# hackeeg-connector-32.net
KiCad netlist of a schematic drawn in EAGLE
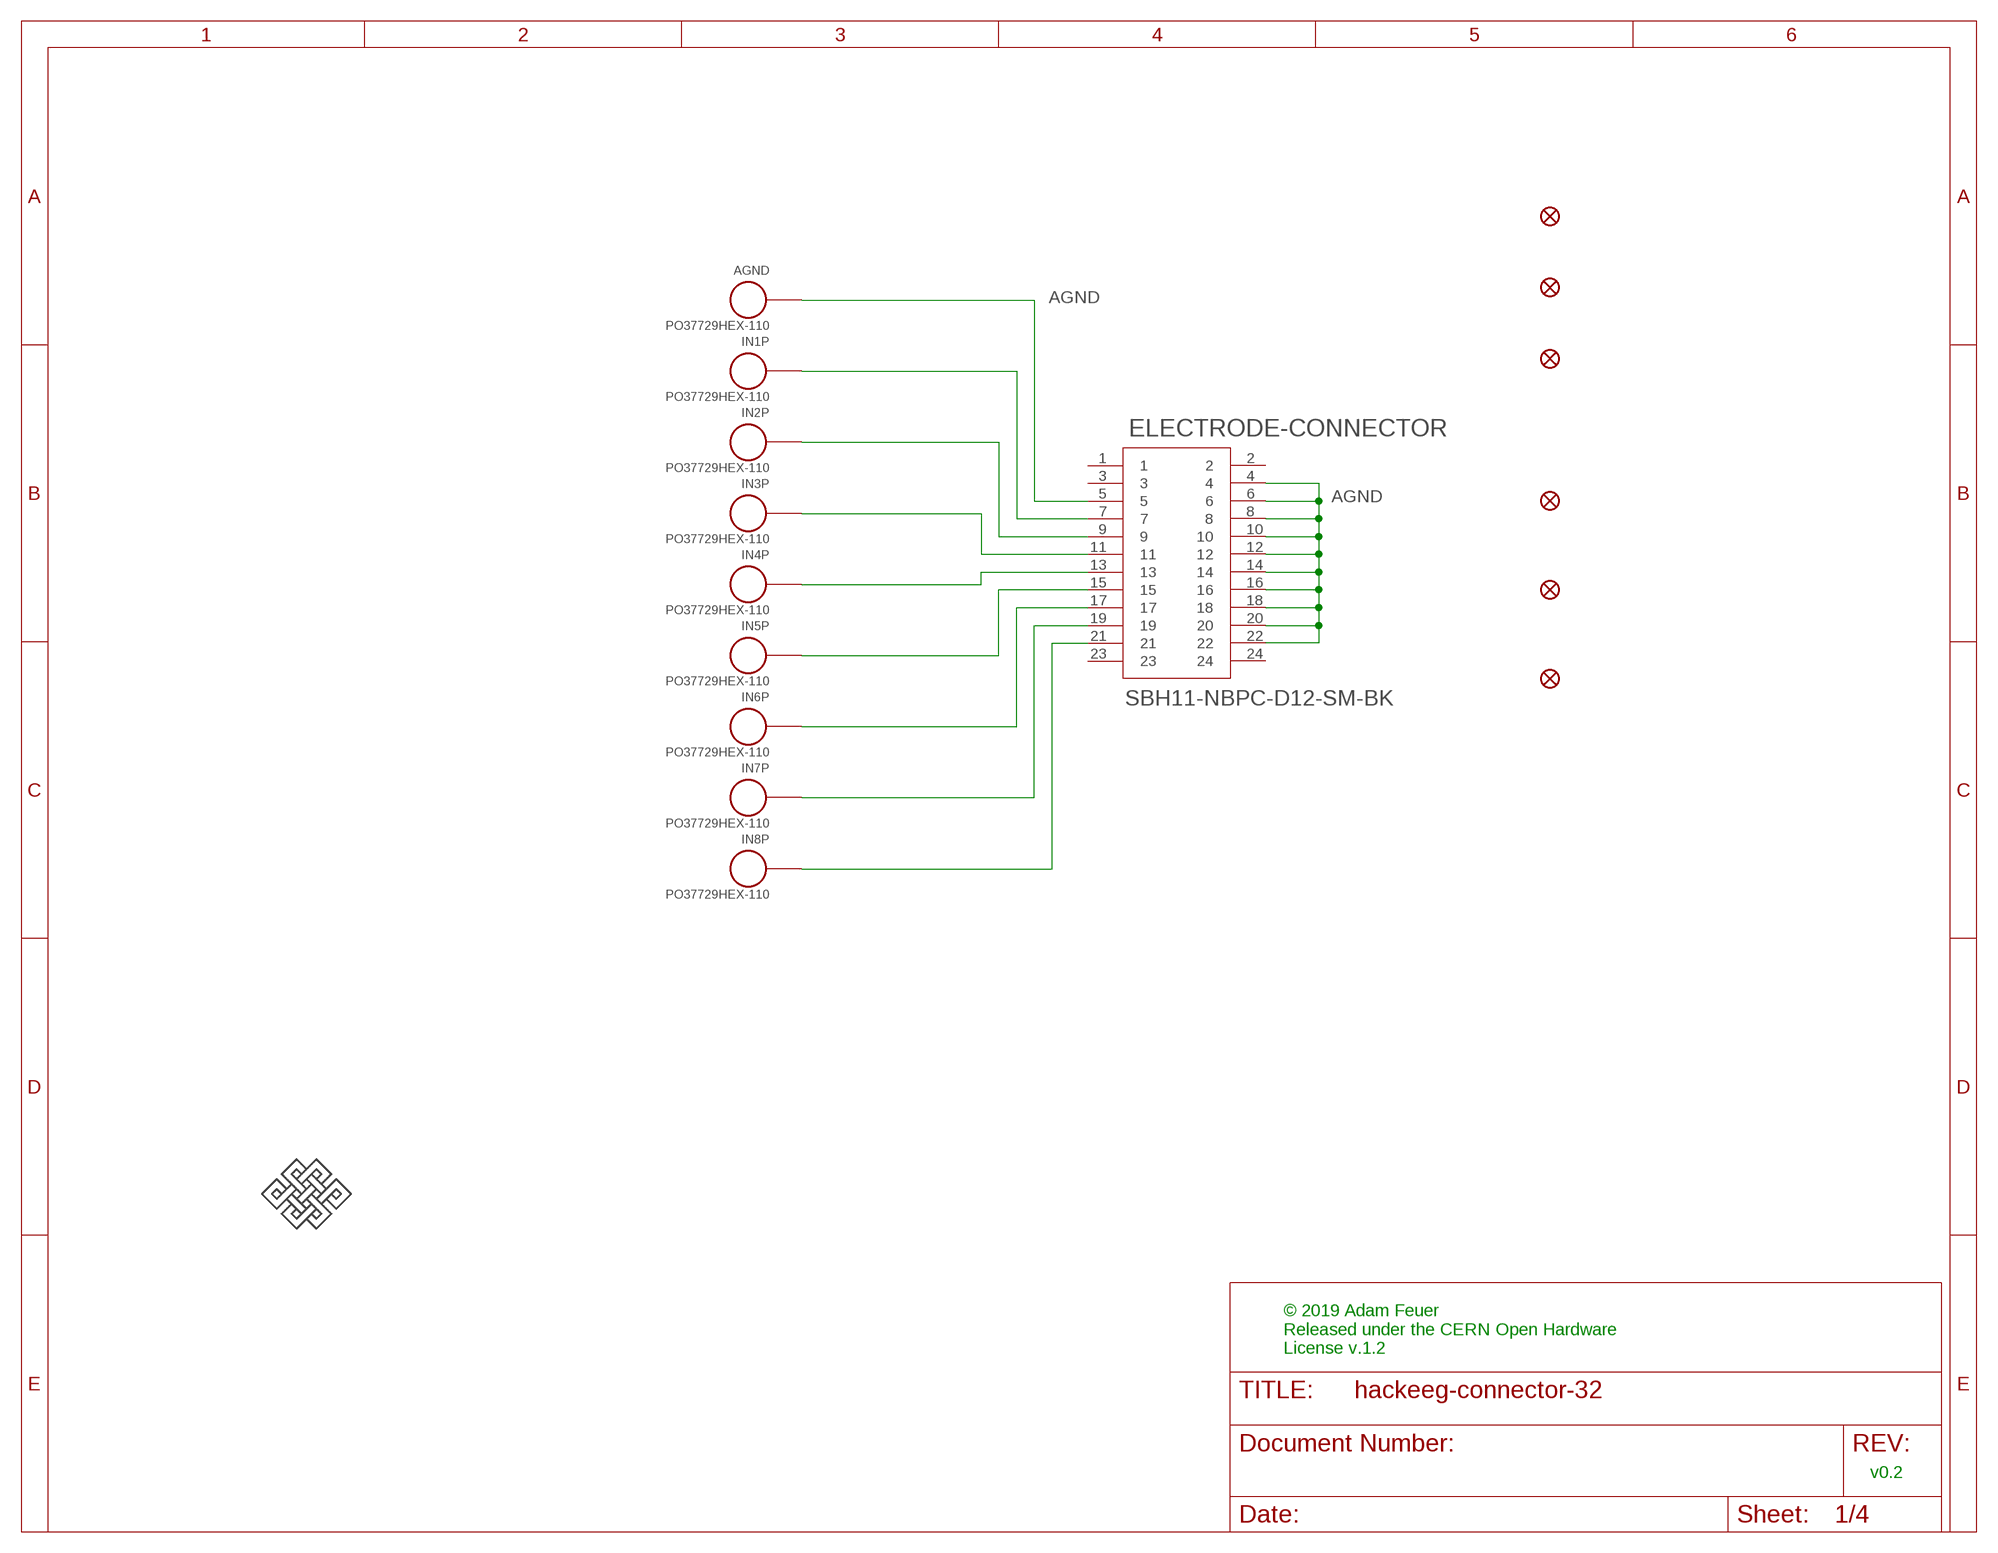
[diagram p0: schematic, sheet 1]
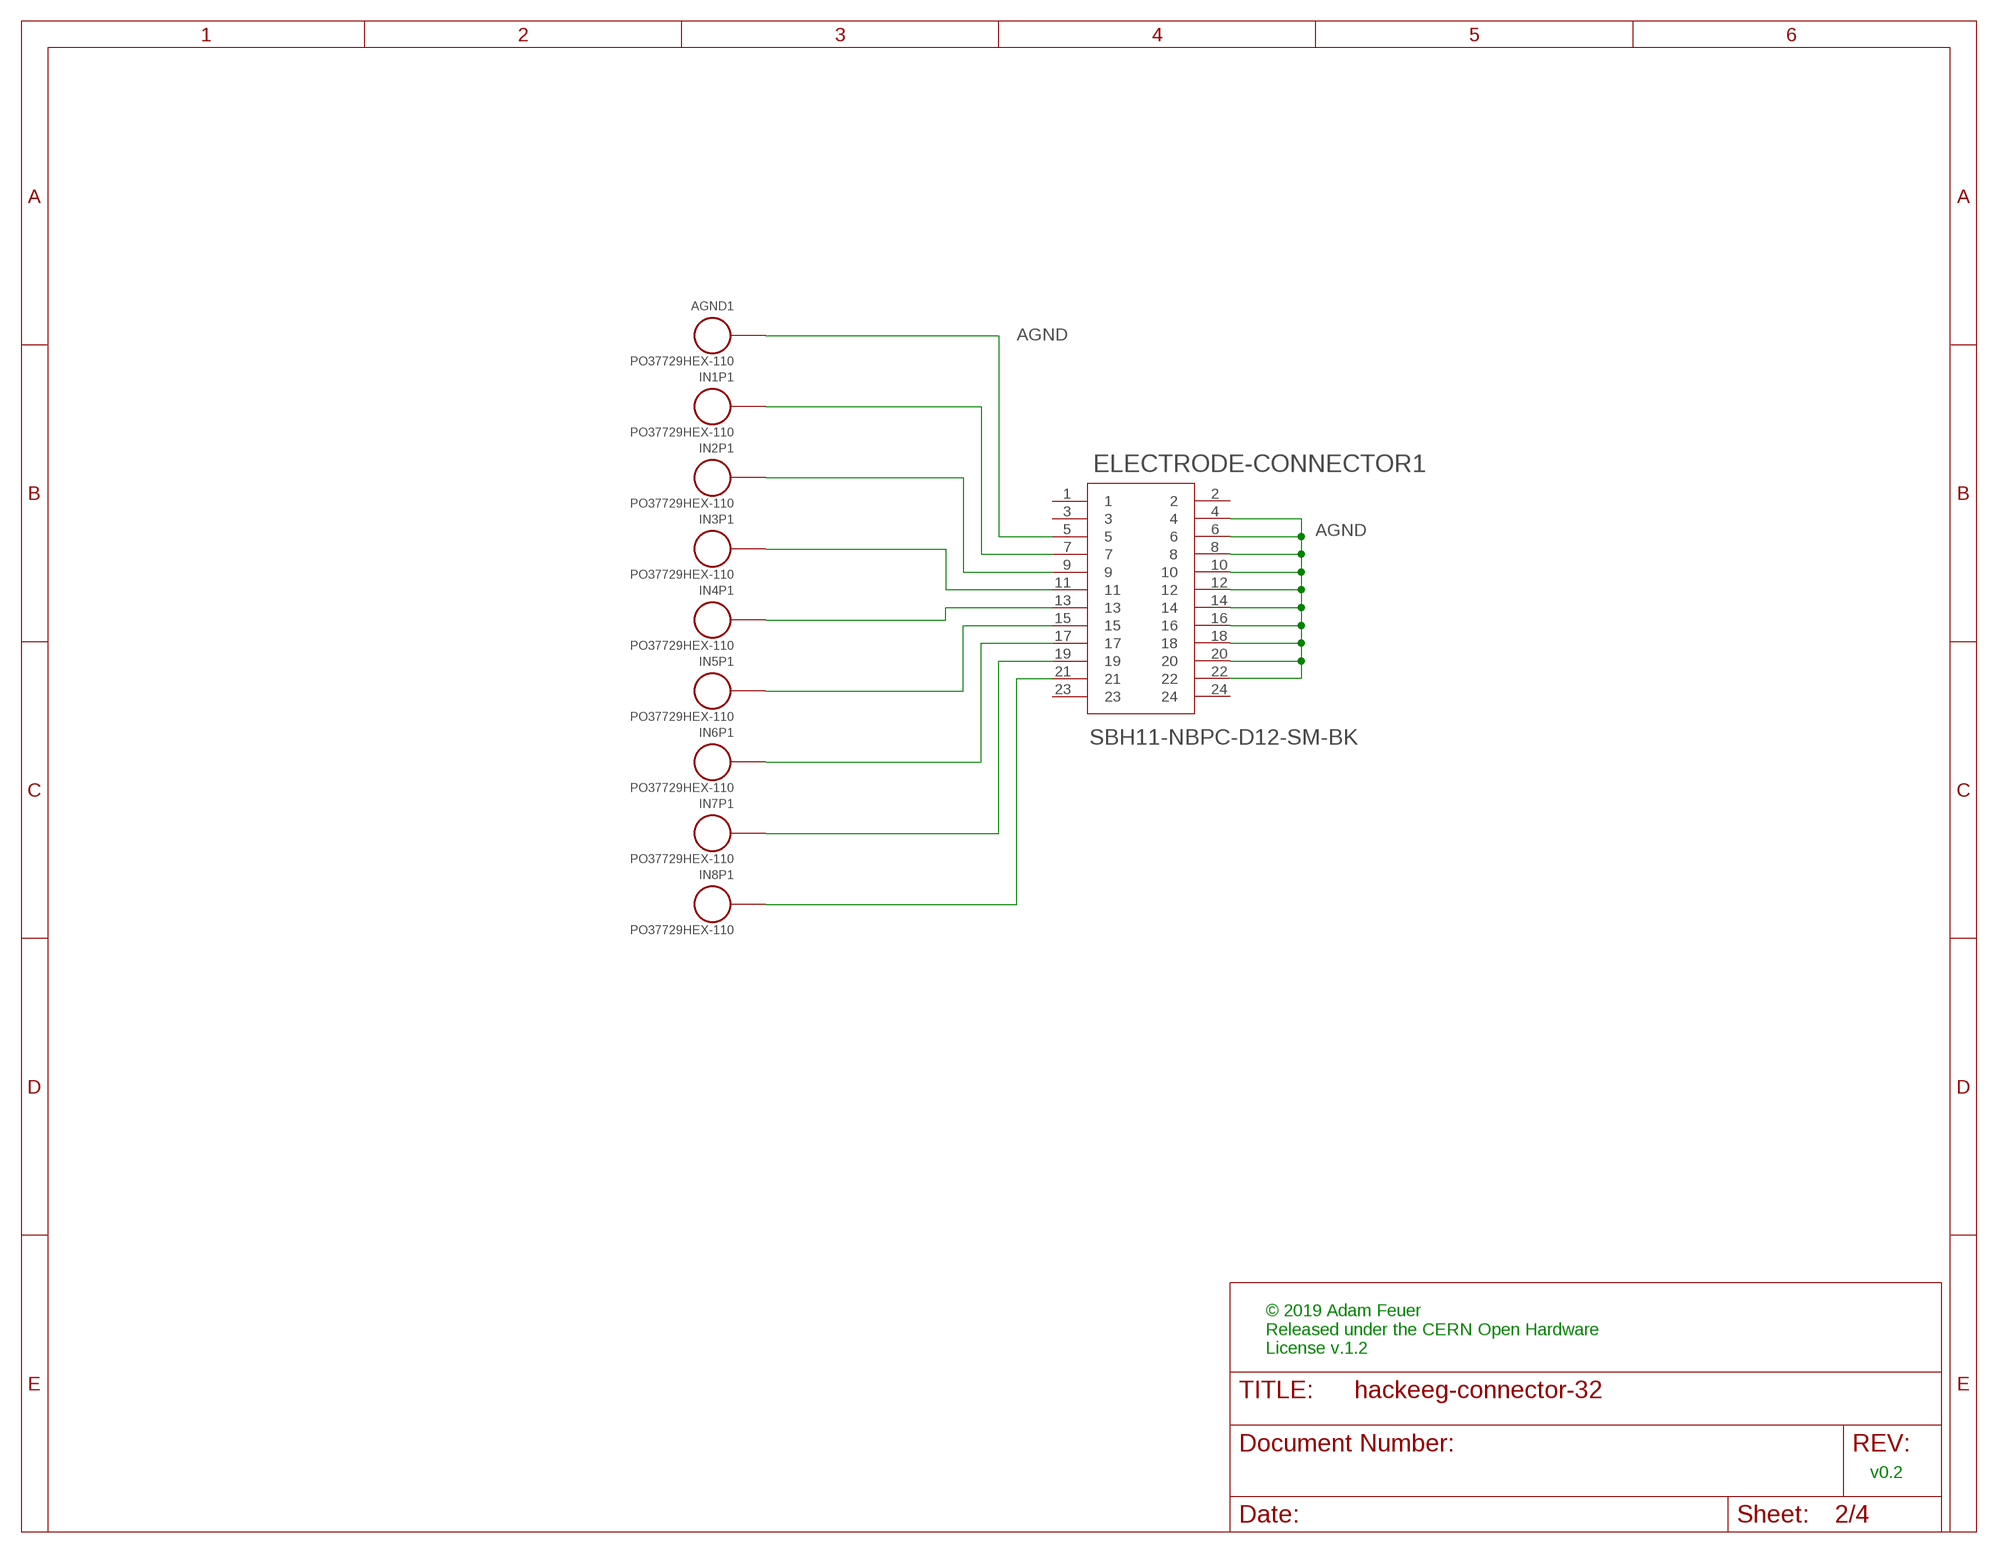
[diagram p1: schematic, sheet 2]
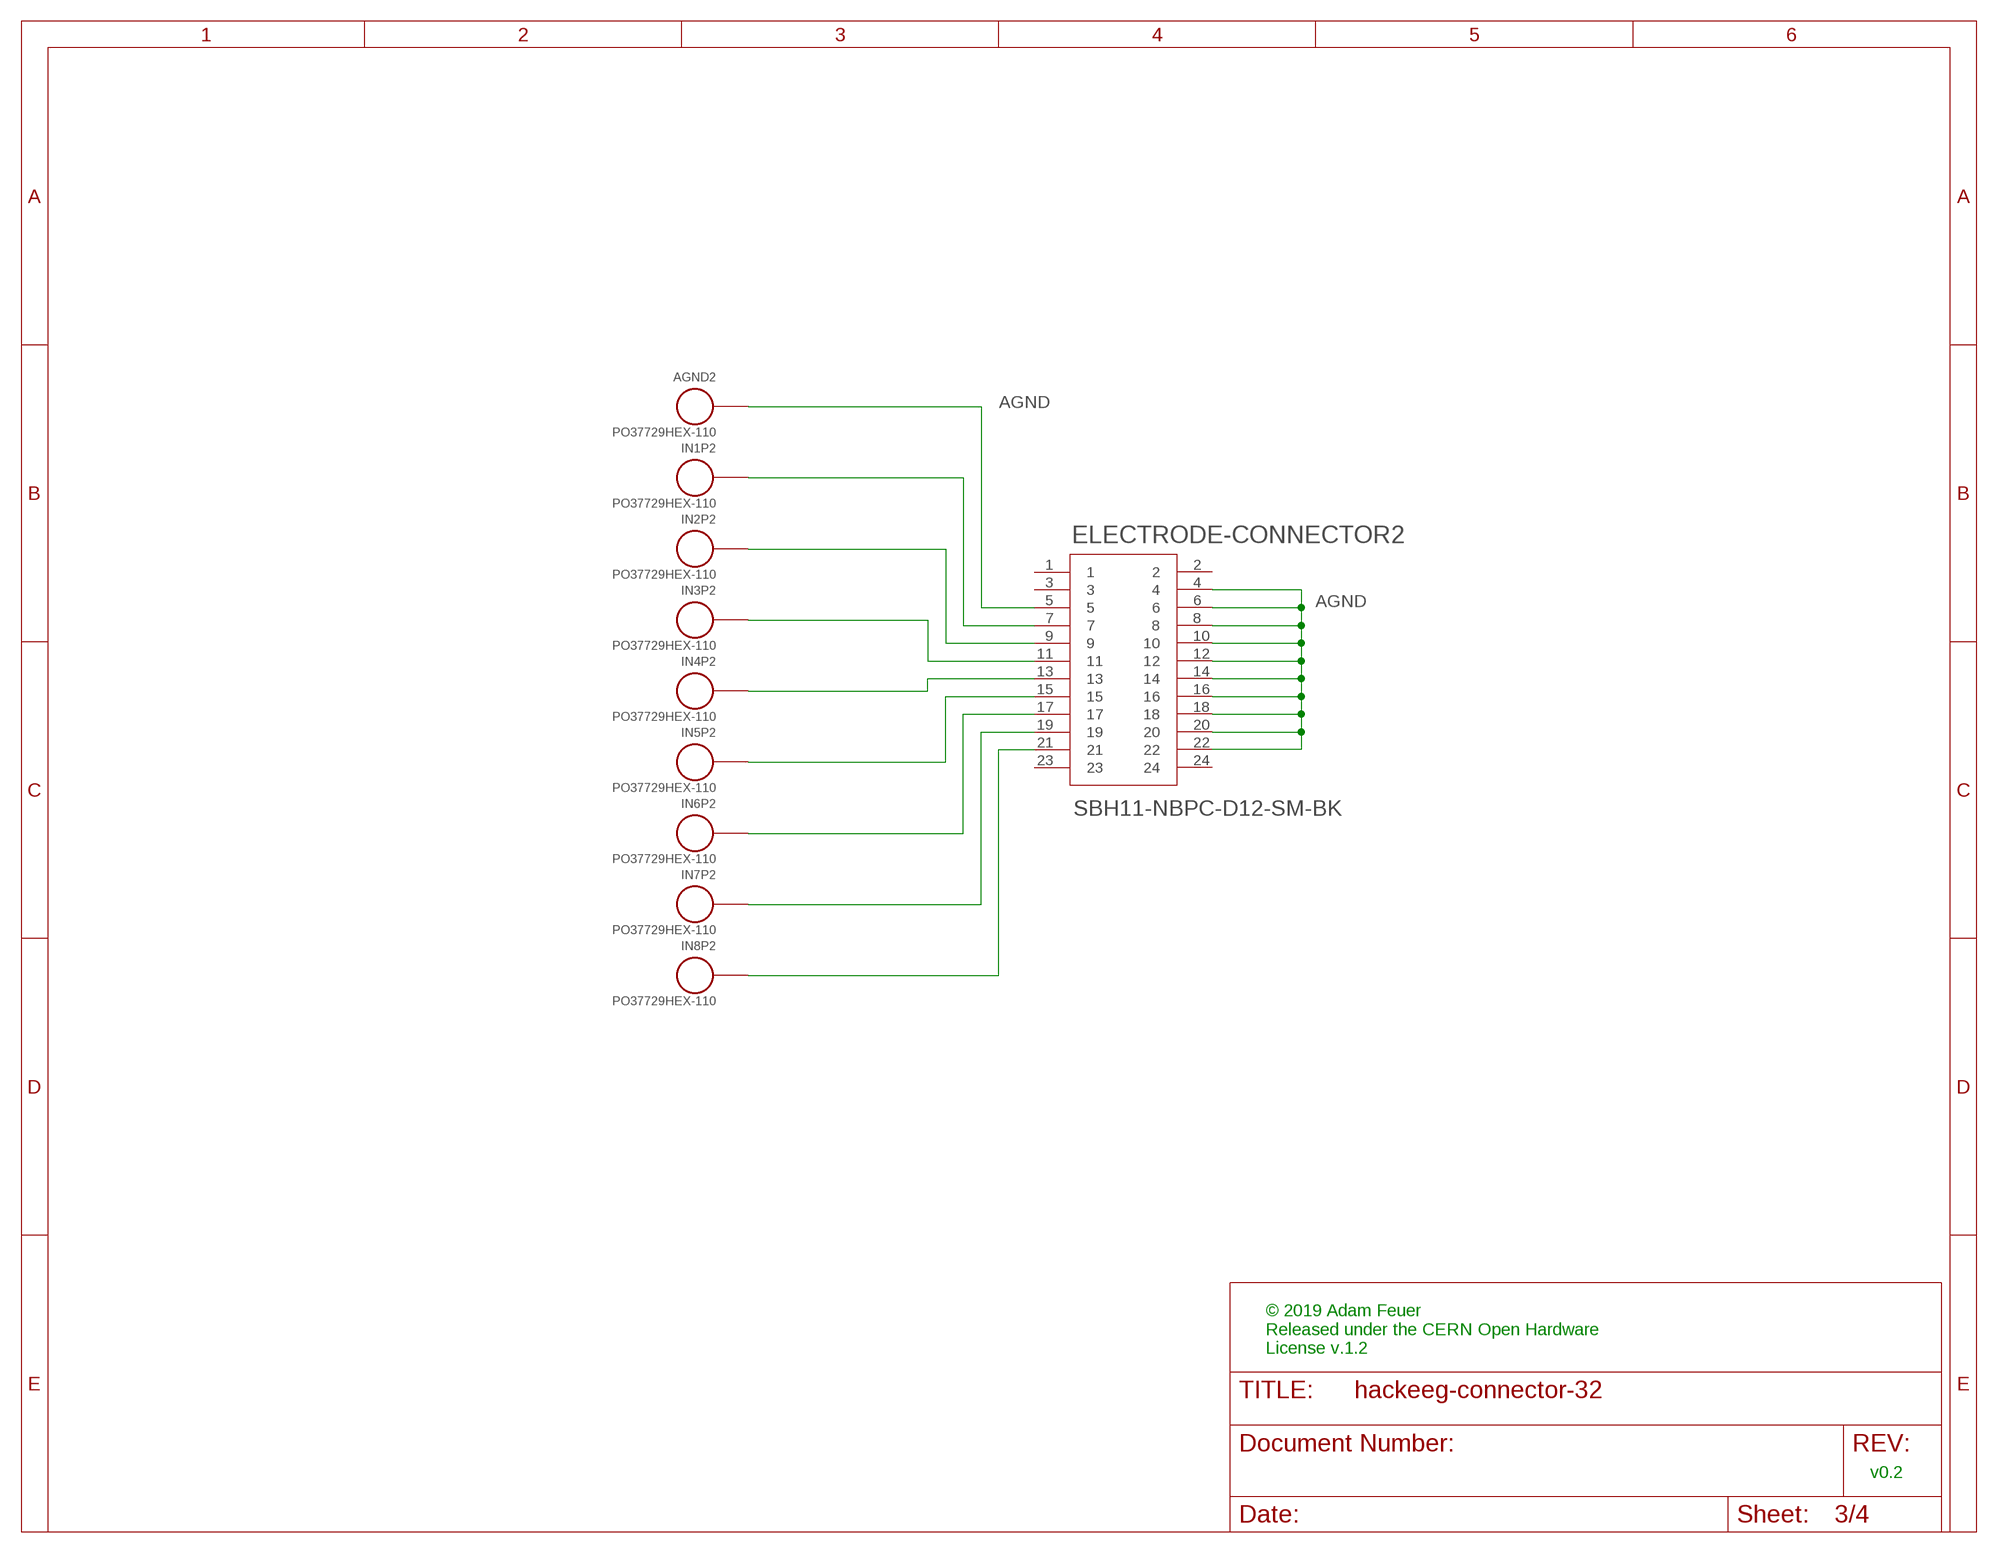
[diagram p2: schematic, sheet 3]
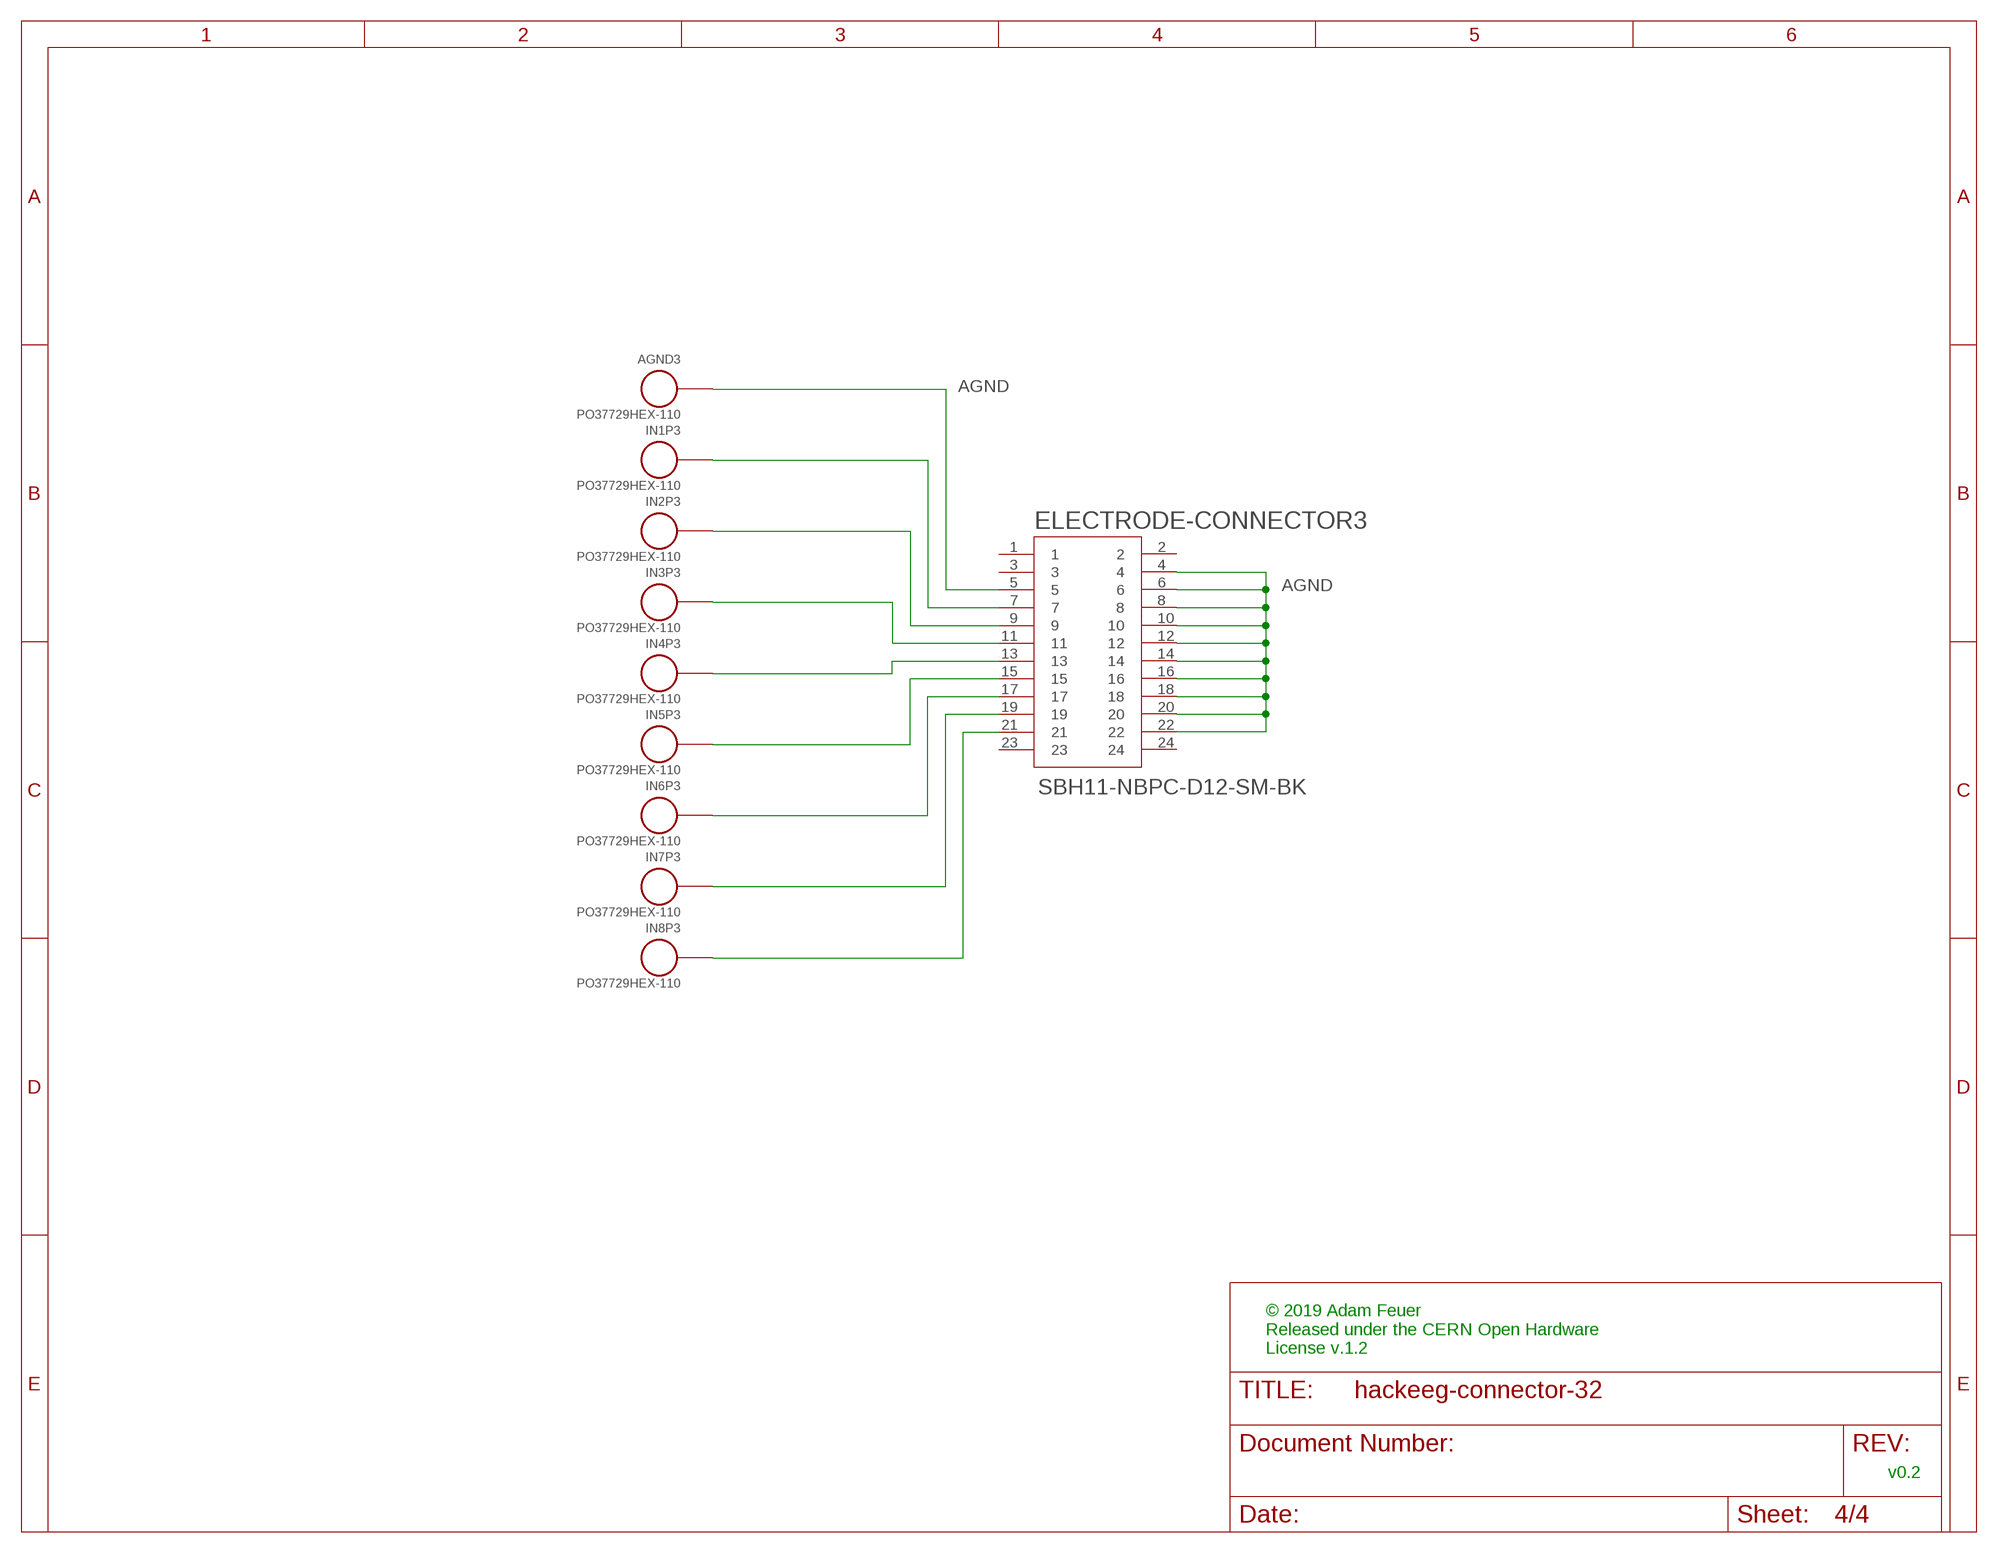
[diagram p3: schematic, sheet 4]

(export (version "E")
  (design (tool "Eeschema 10.0.6"))
  (components
    (comp (ref "AGND2")
      (value "PO37729HEX-110")
      (footprint "eagle-import:HEX-110")
      (libsource (lib "eagle-import") (part "PO37729HEX-110"))
    )
    (comp (ref "ELECTRODE-CONNECTOR2")
      (value "SBH11-NBPC-D12-SM-BK")
      (footprint "eagle-import:SULLINS_SBH11-NBPC-D12-SM-BK")
      (fields (field (name "MF") "Sullins Connector"))
      (libsource (lib "eagle-import") (part "SBH11-NBPC-D12-SM-BK"))
    )
    (comp (ref "IN1P2")
      (value "PO37729HEX-110")
      (footprint "eagle-import:HEX-110")
      (libsource (lib "eagle-import") (part "PO37729HEX-110"))
    )
    (comp (ref "IN2P2")
      (value "PO37729HEX-110")
      (footprint "eagle-import:HEX-110")
      (libsource (lib "eagle-import") (part "PO37729HEX-110"))
    )
    (comp (ref "IN3P2")
      (value "PO37729HEX-110")
      (footprint "eagle-import:HEX-110")
      (libsource (lib "eagle-import") (part "PO37729HEX-110"))
    )
    (comp (ref "IN4P2")
      (value "PO37729HEX-110")
      (footprint "eagle-import:HEX-110")
      (libsource (lib "eagle-import") (part "PO37729HEX-110"))
    )
    (comp (ref "IN5P2")
      (value "PO37729HEX-110")
      (footprint "eagle-import:HEX-110")
      (libsource (lib "eagle-import") (part "PO37729HEX-110"))
    )
    (comp (ref "IN6P2")
      (value "PO37729HEX-110")
      (footprint "eagle-import:HEX-110")
      (libsource (lib "eagle-import") (part "PO37729HEX-110"))
    )
    (comp (ref "IN7P2")
      (value "PO37729HEX-110")
      (footprint "eagle-import:HEX-110")
      (libsource (lib "eagle-import") (part "PO37729HEX-110"))
    )
    (comp (ref "IN8P2")
      (value "PO37729HEX-110")
      (footprint "eagle-import:HEX-110")
      (libsource (lib "eagle-import") (part "PO37729HEX-110"))
    )
    (comp (ref "AGND3")
      (value "PO37729HEX-110")
      (footprint "eagle-import:HEX-110")
      (libsource (lib "eagle-import") (part "PO37729HEX-110"))
    )
    (comp (ref "ELECTRODE-CONNECTOR3")
      (value "SBH11-NBPC-D12-SM-BK")
      (footprint "eagle-import:SULLINS_SBH11-NBPC-D12-SM-BK")
      (fields (field (name "MF") "Sullins Connector"))
      (libsource (lib "eagle-import") (part "SBH11-NBPC-D12-SM-BK"))
    )
    (comp (ref "IN1P3")
      (value "PO37729HEX-110")
      (footprint "eagle-import:HEX-110")
      (libsource (lib "eagle-import") (part "PO37729HEX-110"))
    )
    (comp (ref "IN2P3")
      (value "PO37729HEX-110")
      (footprint "eagle-import:HEX-110")
      (libsource (lib "eagle-import") (part "PO37729HEX-110"))
    )
    (comp (ref "IN3P3")
      (value "PO37729HEX-110")
      (footprint "eagle-import:HEX-110")
      (libsource (lib "eagle-import") (part "PO37729HEX-110"))
    )
    (comp (ref "IN4P3")
      (value "PO37729HEX-110")
      (footprint "eagle-import:HEX-110")
      (libsource (lib "eagle-import") (part "PO37729HEX-110"))
    )
    (comp (ref "IN5P3")
      (value "PO37729HEX-110")
      (footprint "eagle-import:HEX-110")
      (libsource (lib "eagle-import") (part "PO37729HEX-110"))
    )
    (comp (ref "IN6P3")
      (value "PO37729HEX-110")
      (footprint "eagle-import:HEX-110")
      (libsource (lib "eagle-import") (part "PO37729HEX-110"))
    )
    (comp (ref "IN7P3")
      (value "PO37729HEX-110")
      (footprint "eagle-import:HEX-110")
      (libsource (lib "eagle-import") (part "PO37729HEX-110"))
    )
    (comp (ref "IN8P3")
      (value "PO37729HEX-110")
      (footprint "eagle-import:HEX-110")
      (libsource (lib "eagle-import") (part "PO37729HEX-110"))
    )
    (comp (ref "AGND")
      (value "PO37729HEX-110")
      (footprint "eagle-import:HEX-110")
      (libsource (lib "eagle-import") (part "PO37729HEX-110"))
    )
    (comp (ref "ELECTRODE-CONNECTOR")
      (value "SBH11-NBPC-D12-SM-BK")
      (footprint "eagle-import:SULLINS_SBH11-NBPC-D12-SM-BK")
      (fields (field (name "MF") "Sullins Connector"))
      (libsource (lib "eagle-import") (part "SBH11-NBPC-D12-SM-BK"))
    )
    (comp (ref "FD1")
      (value "FIDUCIAL1X2")
      (footprint "eagle-import:FIDUCIAL-1X2")
      (libsource (lib "eagle-import") (part "FIDUCIAL1X2"))
    )
    (comp (ref "FD2")
      (value "FIDUCIAL1X2")
      (footprint "eagle-import:FIDUCIAL-1X2")
      (libsource (lib "eagle-import") (part "FIDUCIAL1X2"))
    )
    (comp (ref "FD3")
      (value "FIDUCIAL1X2")
      (footprint "eagle-import:FIDUCIAL-1X2")
      (libsource (lib "eagle-import") (part "FIDUCIAL1X2"))
    )
    (comp (ref "FD4")
      (value "FIDUCIAL1X2")
      (footprint "eagle-import:FIDUCIAL-1X2")
      (libsource (lib "eagle-import") (part "FIDUCIAL1X2"))
    )
    (comp (ref "FD5")
      (value "FIDUCIAL1X2")
      (footprint "eagle-import:FIDUCIAL-1X2")
      (libsource (lib "eagle-import") (part "FIDUCIAL1X2"))
    )
    (comp (ref "FD6")
      (value "FIDUCIAL1X2")
      (footprint "eagle-import:FIDUCIAL-1X2")
      (libsource (lib "eagle-import") (part "FIDUCIAL1X2"))
    )
    (comp (ref "IN1P")
      (value "PO37729HEX-110")
      (footprint "eagle-import:HEX-110")
      (libsource (lib "eagle-import") (part "PO37729HEX-110"))
    )
    (comp (ref "IN2P")
      (value "PO37729HEX-110")
      (footprint "eagle-import:HEX-110")
      (libsource (lib "eagle-import") (part "PO37729HEX-110"))
    )
    (comp (ref "IN3P")
      (value "PO37729HEX-110")
      (footprint "eagle-import:HEX-110")
      (libsource (lib "eagle-import") (part "PO37729HEX-110"))
    )
    (comp (ref "IN4P")
      (value "PO37729HEX-110")
      (footprint "eagle-import:HEX-110")
      (libsource (lib "eagle-import") (part "PO37729HEX-110"))
    )
    (comp (ref "IN5P")
      (value "PO37729HEX-110")
      (footprint "eagle-import:HEX-110")
      (libsource (lib "eagle-import") (part "PO37729HEX-110"))
    )
    (comp (ref "IN6P")
      (value "PO37729HEX-110")
      (footprint "eagle-import:HEX-110")
      (libsource (lib "eagle-import") (part "PO37729HEX-110"))
    )
    (comp (ref "IN7P")
      (value "PO37729HEX-110")
      (footprint "eagle-import:HEX-110")
      (libsource (lib "eagle-import") (part "PO37729HEX-110"))
    )
    (comp (ref "IN8P")
      (value "PO37729HEX-110")
      (footprint "eagle-import:HEX-110")
      (libsource (lib "eagle-import") (part "PO37729HEX-110"))
    )
    (comp (ref "U$1")
      (value "ENDLESSKNOTENDLESSKNOT-MEDIUM")
      (footprint "eagle-import:ENDLESSKNOT-MEDIUM")
      (libsource (lib "eagle-import") (part "ENDLESSKNOTENDLESSKNOT-MEDIUM"))
    )
    (comp (ref "AGND1")
      (value "PO37729HEX-110")
      (footprint "eagle-import:HEX-110")
      (libsource (lib "eagle-import") (part "PO37729HEX-110"))
    )
    (comp (ref "ELECTRODE-CONNECTOR1")
      (value "SBH11-NBPC-D12-SM-BK")
      (footprint "eagle-import:SULLINS_SBH11-NBPC-D12-SM-BK")
      (fields (field (name "MF") "Sullins Connector"))
      (libsource (lib "eagle-import") (part "SBH11-NBPC-D12-SM-BK"))
    )
    (comp (ref "IN1P1")
      (value "PO37729HEX-110")
      (footprint "eagle-import:HEX-110")
      (libsource (lib "eagle-import") (part "PO37729HEX-110"))
    )
    (comp (ref "IN2P1")
      (value "PO37729HEX-110")
      (footprint "eagle-import:HEX-110")
      (libsource (lib "eagle-import") (part "PO37729HEX-110"))
    )
    (comp (ref "IN3P1")
      (value "PO37729HEX-110")
      (footprint "eagle-import:HEX-110")
      (libsource (lib "eagle-import") (part "PO37729HEX-110"))
    )
    (comp (ref "IN4P1")
      (value "PO37729HEX-110")
      (footprint "eagle-import:HEX-110")
      (libsource (lib "eagle-import") (part "PO37729HEX-110"))
    )
    (comp (ref "IN5P1")
      (value "PO37729HEX-110")
      (footprint "eagle-import:HEX-110")
      (libsource (lib "eagle-import") (part "PO37729HEX-110"))
    )
    (comp (ref "IN6P1")
      (value "PO37729HEX-110")
      (footprint "eagle-import:HEX-110")
      (libsource (lib "eagle-import") (part "PO37729HEX-110"))
    )
    (comp (ref "IN7P1")
      (value "PO37729HEX-110")
      (footprint "eagle-import:HEX-110")
      (libsource (lib "eagle-import") (part "PO37729HEX-110"))
    )
    (comp (ref "IN8P1")
      (value "PO37729HEX-110")
      (footprint "eagle-import:HEX-110")
      (libsource (lib "eagle-import") (part "PO37729HEX-110"))
    )
  )
  (nets
    (net (code "1") (name "AGND") (class "Default")
      (node (ref "AGND") (pin "SIGNAL") (pinfunction "SIGNAL_SIGNAL") (pintype "bidirectional"))
      (node (ref "AGND1") (pin "SIGNAL") (pinfunction "SIGNAL_SIGNAL") (pintype "bidirectional"))
      (node (ref "AGND2") (pin "SIGNAL") (pinfunction "SIGNAL_SIGNAL") (pintype "bidirectional"))
      (node (ref "AGND3") (pin "SIGNAL") (pinfunction "SIGNAL_SIGNAL") (pintype "bidirectional"))
      (node (ref "ELECTRODE-CONNECTOR") (pin "10") (pinfunction "10_10") (pintype "passive"))
      (node (ref "ELECTRODE-CONNECTOR") (pin "12") (pinfunction "12_12") (pintype "passive"))
      (node (ref "ELECTRODE-CONNECTOR") (pin "14") (pinfunction "14_14") (pintype "passive"))
      (node (ref "ELECTRODE-CONNECTOR") (pin "16") (pinfunction "16_16") (pintype "passive"))
      (node (ref "ELECTRODE-CONNECTOR") (pin "18") (pinfunction "18_18") (pintype "passive"))
      (node (ref "ELECTRODE-CONNECTOR") (pin "20") (pinfunction "20_20") (pintype "passive"))
      (node (ref "ELECTRODE-CONNECTOR") (pin "22") (pinfunction "22_22") (pintype "passive"))
      (node (ref "ELECTRODE-CONNECTOR") (pin "4") (pinfunction "4_4") (pintype "passive"))
      (node (ref "ELECTRODE-CONNECTOR") (pin "5") (pinfunction "5_5") (pintype "passive"))
      (node (ref "ELECTRODE-CONNECTOR") (pin "6") (pinfunction "6_6") (pintype "passive"))
      (node (ref "ELECTRODE-CONNECTOR") (pin "8") (pinfunction "8_8") (pintype "passive"))
      (node (ref "ELECTRODE-CONNECTOR1") (pin "10") (pinfunction "10_10") (pintype "passive"))
      (node (ref "ELECTRODE-CONNECTOR1") (pin "12") (pinfunction "12_12") (pintype "passive"))
      (node (ref "ELECTRODE-CONNECTOR1") (pin "14") (pinfunction "14_14") (pintype "passive"))
      (node (ref "ELECTRODE-CONNECTOR1") (pin "16") (pinfunction "16_16") (pintype "passive"))
      (node (ref "ELECTRODE-CONNECTOR1") (pin "18") (pinfunction "18_18") (pintype "passive"))
      (node (ref "ELECTRODE-CONNECTOR1") (pin "20") (pinfunction "20_20") (pintype "passive"))
      (node (ref "ELECTRODE-CONNECTOR1") (pin "22") (pinfunction "22_22") (pintype "passive"))
      (node (ref "ELECTRODE-CONNECTOR1") (pin "4") (pinfunction "4_4") (pintype "passive"))
      (node (ref "ELECTRODE-CONNECTOR1") (pin "5") (pinfunction "5_5") (pintype "passive"))
      (node (ref "ELECTRODE-CONNECTOR1") (pin "6") (pinfunction "6_6") (pintype "passive"))
      (node (ref "ELECTRODE-CONNECTOR1") (pin "8") (pinfunction "8_8") (pintype "passive"))
      (node (ref "ELECTRODE-CONNECTOR2") (pin "10") (pinfunction "10_10") (pintype "passive"))
      (node (ref "ELECTRODE-CONNECTOR2") (pin "12") (pinfunction "12_12") (pintype "passive"))
      (node (ref "ELECTRODE-CONNECTOR2") (pin "14") (pinfunction "14_14") (pintype "passive"))
      (node (ref "ELECTRODE-CONNECTOR2") (pin "16") (pinfunction "16_16") (pintype "passive"))
      (node (ref "ELECTRODE-CONNECTOR2") (pin "18") (pinfunction "18_18") (pintype "passive"))
      (node (ref "ELECTRODE-CONNECTOR2") (pin "20") (pinfunction "20_20") (pintype "passive"))
      (node (ref "ELECTRODE-CONNECTOR2") (pin "22") (pinfunction "22_22") (pintype "passive"))
      (node (ref "ELECTRODE-CONNECTOR2") (pin "4") (pinfunction "4_4") (pintype "passive"))
      (node (ref "ELECTRODE-CONNECTOR2") (pin "5") (pinfunction "5_5") (pintype "passive"))
      (node (ref "ELECTRODE-CONNECTOR2") (pin "6") (pinfunction "6_6") (pintype "passive"))
      (node (ref "ELECTRODE-CONNECTOR2") (pin "8") (pinfunction "8_8") (pintype "passive"))
      (node (ref "ELECTRODE-CONNECTOR3") (pin "10") (pinfunction "10_10") (pintype "passive"))
      (node (ref "ELECTRODE-CONNECTOR3") (pin "12") (pinfunction "12_12") (pintype "passive"))
      (node (ref "ELECTRODE-CONNECTOR3") (pin "14") (pinfunction "14_14") (pintype "passive"))
      (node (ref "ELECTRODE-CONNECTOR3") (pin "16") (pinfunction "16_16") (pintype "passive"))
      (node (ref "ELECTRODE-CONNECTOR3") (pin "18") (pinfunction "18_18") (pintype "passive"))
      (node (ref "ELECTRODE-CONNECTOR3") (pin "20") (pinfunction "20_20") (pintype "passive"))
      (node (ref "ELECTRODE-CONNECTOR3") (pin "22") (pinfunction "22_22") (pintype "passive"))
      (node (ref "ELECTRODE-CONNECTOR3") (pin "4") (pinfunction "4_4") (pintype "passive"))
      (node (ref "ELECTRODE-CONNECTOR3") (pin "5") (pinfunction "5_5") (pintype "passive"))
      (node (ref "ELECTRODE-CONNECTOR3") (pin "6") (pinfunction "6_6") (pintype "passive"))
      (node (ref "ELECTRODE-CONNECTOR3") (pin "8") (pinfunction "8_8") (pintype "passive"))
    )
    (net (code "2") (name "Net-(ELECTRODE-CONNECTOR-Pad7)") (class "Default")
      (node (ref "ELECTRODE-CONNECTOR") (pin "7") (pinfunction "7_7") (pintype "passive"))
      (node (ref "IN1P") (pin "SIGNAL") (pinfunction "SIGNAL_SIGNAL") (pintype "bidirectional"))
    )
    (net (code "3") (name "Net-(ELECTRODE-CONNECTOR-Pad9)") (class "Default")
      (node (ref "ELECTRODE-CONNECTOR") (pin "9") (pinfunction "9_9") (pintype "passive"))
      (node (ref "IN2P") (pin "SIGNAL") (pinfunction "SIGNAL_SIGNAL") (pintype "bidirectional"))
    )
    (net (code "4") (name "Net-(ELECTRODE-CONNECTOR-Pad11)") (class "Default")
      (node (ref "ELECTRODE-CONNECTOR") (pin "11") (pinfunction "11_11") (pintype "passive"))
      (node (ref "IN3P") (pin "SIGNAL") (pinfunction "SIGNAL_SIGNAL") (pintype "bidirectional"))
    )
    (net (code "5") (name "Net-(ELECTRODE-CONNECTOR-Pad13)") (class "Default")
      (node (ref "ELECTRODE-CONNECTOR") (pin "13") (pinfunction "13_13") (pintype "passive"))
      (node (ref "IN4P") (pin "SIGNAL") (pinfunction "SIGNAL_SIGNAL") (pintype "bidirectional"))
    )
    (net (code "6") (name "Net-(ELECTRODE-CONNECTOR-Pad15)") (class "Default")
      (node (ref "ELECTRODE-CONNECTOR") (pin "15") (pinfunction "15_15") (pintype "passive"))
      (node (ref "IN5P") (pin "SIGNAL") (pinfunction "SIGNAL_SIGNAL") (pintype "bidirectional"))
    )
    (net (code "7") (name "Net-(ELECTRODE-CONNECTOR-Pad17)") (class "Default")
      (node (ref "ELECTRODE-CONNECTOR") (pin "17") (pinfunction "17_17") (pintype "passive"))
      (node (ref "IN6P") (pin "SIGNAL") (pinfunction "SIGNAL_SIGNAL") (pintype "bidirectional"))
    )
    (net (code "8") (name "Net-(ELECTRODE-CONNECTOR-Pad19)") (class "Default")
      (node (ref "ELECTRODE-CONNECTOR") (pin "19") (pinfunction "19_19") (pintype "passive"))
      (node (ref "IN7P") (pin "SIGNAL") (pinfunction "SIGNAL_SIGNAL") (pintype "bidirectional"))
    )
    (net (code "9") (name "Net-(ELECTRODE-CONNECTOR-Pad21)") (class "Default")
      (node (ref "ELECTRODE-CONNECTOR") (pin "21") (pinfunction "21_21") (pintype "passive"))
      (node (ref "IN8P") (pin "SIGNAL") (pinfunction "SIGNAL_SIGNAL") (pintype "bidirectional"))
    )
    (net (code "10") (name "Net-(ELECTRODE-CONNECTOR1-Pad7)") (class "Default")
      (node (ref "ELECTRODE-CONNECTOR1") (pin "7") (pinfunction "7_7") (pintype "passive"))
      (node (ref "IN1P1") (pin "SIGNAL") (pinfunction "SIGNAL_SIGNAL") (pintype "bidirectional"))
    )
    (net (code "11") (name "Net-(ELECTRODE-CONNECTOR1-Pad9)") (class "Default")
      (node (ref "ELECTRODE-CONNECTOR1") (pin "9") (pinfunction "9_9") (pintype "passive"))
      (node (ref "IN2P1") (pin "SIGNAL") (pinfunction "SIGNAL_SIGNAL") (pintype "bidirectional"))
    )
    (net (code "12") (name "Net-(ELECTRODE-CONNECTOR1-Pad11)") (class "Default")
      (node (ref "ELECTRODE-CONNECTOR1") (pin "11") (pinfunction "11_11") (pintype "passive"))
      (node (ref "IN3P1") (pin "SIGNAL") (pinfunction "SIGNAL_SIGNAL") (pintype "bidirectional"))
    )
    (net (code "13") (name "Net-(ELECTRODE-CONNECTOR1-Pad13)") (class "Default")
      (node (ref "ELECTRODE-CONNECTOR1") (pin "13") (pinfunction "13_13") (pintype "passive"))
      (node (ref "IN4P1") (pin "SIGNAL") (pinfunction "SIGNAL_SIGNAL") (pintype "bidirectional"))
    )
    (net (code "14") (name "Net-(ELECTRODE-CONNECTOR1-Pad15)") (class "Default")
      (node (ref "ELECTRODE-CONNECTOR1") (pin "15") (pinfunction "15_15") (pintype "passive"))
      (node (ref "IN5P1") (pin "SIGNAL") (pinfunction "SIGNAL_SIGNAL") (pintype "bidirectional"))
    )
    (net (code "15") (name "Net-(ELECTRODE-CONNECTOR1-Pad17)") (class "Default")
      (node (ref "ELECTRODE-CONNECTOR1") (pin "17") (pinfunction "17_17") (pintype "passive"))
      (node (ref "IN6P1") (pin "SIGNAL") (pinfunction "SIGNAL_SIGNAL") (pintype "bidirectional"))
    )
    (net (code "16") (name "Net-(ELECTRODE-CONNECTOR1-Pad19)") (class "Default")
      (node (ref "ELECTRODE-CONNECTOR1") (pin "19") (pinfunction "19_19") (pintype "passive"))
      (node (ref "IN7P1") (pin "SIGNAL") (pinfunction "SIGNAL_SIGNAL") (pintype "bidirectional"))
    )
    (net (code "17") (name "Net-(ELECTRODE-CONNECTOR1-Pad21)") (class "Default")
      (node (ref "ELECTRODE-CONNECTOR1") (pin "21") (pinfunction "21_21") (pintype "passive"))
      (node (ref "IN8P1") (pin "SIGNAL") (pinfunction "SIGNAL_SIGNAL") (pintype "bidirectional"))
    )
    (net (code "18") (name "Net-(ELECTRODE-CONNECTOR2-Pad7)") (class "Default")
      (node (ref "ELECTRODE-CONNECTOR2") (pin "7") (pinfunction "7_7") (pintype "passive"))
      (node (ref "IN1P2") (pin "SIGNAL") (pinfunction "SIGNAL_SIGNAL") (pintype "bidirectional"))
    )
    (net (code "19") (name "Net-(ELECTRODE-CONNECTOR2-Pad9)") (class "Default")
      (node (ref "ELECTRODE-CONNECTOR2") (pin "9") (pinfunction "9_9") (pintype "passive"))
      (node (ref "IN2P2") (pin "SIGNAL") (pinfunction "SIGNAL_SIGNAL") (pintype "bidirectional"))
    )
    (net (code "20") (name "Net-(ELECTRODE-CONNECTOR2-Pad11)") (class "Default")
      (node (ref "ELECTRODE-CONNECTOR2") (pin "11") (pinfunction "11_11") (pintype "passive"))
      (node (ref "IN3P2") (pin "SIGNAL") (pinfunction "SIGNAL_SIGNAL") (pintype "bidirectional"))
    )
    (net (code "21") (name "Net-(ELECTRODE-CONNECTOR2-Pad13)") (class "Default")
      (node (ref "ELECTRODE-CONNECTOR2") (pin "13") (pinfunction "13_13") (pintype "passive"))
      (node (ref "IN4P2") (pin "SIGNAL") (pinfunction "SIGNAL_SIGNAL") (pintype "bidirectional"))
    )
    (net (code "22") (name "Net-(ELECTRODE-CONNECTOR2-Pad15)") (class "Default")
      (node (ref "ELECTRODE-CONNECTOR2") (pin "15") (pinfunction "15_15") (pintype "passive"))
      (node (ref "IN5P2") (pin "SIGNAL") (pinfunction "SIGNAL_SIGNAL") (pintype "bidirectional"))
    )
    (net (code "23") (name "Net-(ELECTRODE-CONNECTOR2-Pad17)") (class "Default")
      (node (ref "ELECTRODE-CONNECTOR2") (pin "17") (pinfunction "17_17") (pintype "passive"))
      (node (ref "IN6P2") (pin "SIGNAL") (pinfunction "SIGNAL_SIGNAL") (pintype "bidirectional"))
    )
    (net (code "24") (name "Net-(ELECTRODE-CONNECTOR2-Pad19)") (class "Default")
      (node (ref "ELECTRODE-CONNECTOR2") (pin "19") (pinfunction "19_19") (pintype "passive"))
      (node (ref "IN7P2") (pin "SIGNAL") (pinfunction "SIGNAL_SIGNAL") (pintype "bidirectional"))
    )
    (net (code "25") (name "Net-(ELECTRODE-CONNECTOR2-Pad21)") (class "Default")
      (node (ref "ELECTRODE-CONNECTOR2") (pin "21") (pinfunction "21_21") (pintype "passive"))
      (node (ref "IN8P2") (pin "SIGNAL") (pinfunction "SIGNAL_SIGNAL") (pintype "bidirectional"))
    )
    (net (code "26") (name "Net-(ELECTRODE-CONNECTOR3-Pad7)") (class "Default")
      (node (ref "ELECTRODE-CONNECTOR3") (pin "7") (pinfunction "7_7") (pintype "passive"))
      (node (ref "IN1P3") (pin "SIGNAL") (pinfunction "SIGNAL_SIGNAL") (pintype "bidirectional"))
    )
    (net (code "27") (name "Net-(ELECTRODE-CONNECTOR3-Pad9)") (class "Default")
      (node (ref "ELECTRODE-CONNECTOR3") (pin "9") (pinfunction "9_9") (pintype "passive"))
      (node (ref "IN2P3") (pin "SIGNAL") (pinfunction "SIGNAL_SIGNAL") (pintype "bidirectional"))
    )
    (net (code "28") (name "Net-(ELECTRODE-CONNECTOR3-Pad11)") (class "Default")
      (node (ref "ELECTRODE-CONNECTOR3") (pin "11") (pinfunction "11_11") (pintype "passive"))
      (node (ref "IN3P3") (pin "SIGNAL") (pinfunction "SIGNAL_SIGNAL") (pintype "bidirectional"))
    )
    (net (code "29") (name "Net-(ELECTRODE-CONNECTOR3-Pad13)") (class "Default")
      (node (ref "ELECTRODE-CONNECTOR3") (pin "13") (pinfunction "13_13") (pintype "passive"))
      (node (ref "IN4P3") (pin "SIGNAL") (pinfunction "SIGNAL_SIGNAL") (pintype "bidirectional"))
    )
    (net (code "30") (name "Net-(ELECTRODE-CONNECTOR3-Pad15)") (class "Default")
      (node (ref "ELECTRODE-CONNECTOR3") (pin "15") (pinfunction "15_15") (pintype "passive"))
      (node (ref "IN5P3") (pin "SIGNAL") (pinfunction "SIGNAL_SIGNAL") (pintype "bidirectional"))
    )
    (net (code "31") (name "Net-(ELECTRODE-CONNECTOR3-Pad17)") (class "Default")
      (node (ref "ELECTRODE-CONNECTOR3") (pin "17") (pinfunction "17_17") (pintype "passive"))
      (node (ref "IN6P3") (pin "SIGNAL") (pinfunction "SIGNAL_SIGNAL") (pintype "bidirectional"))
    )
    (net (code "32") (name "Net-(ELECTRODE-CONNECTOR3-Pad19)") (class "Default")
      (node (ref "ELECTRODE-CONNECTOR3") (pin "19") (pinfunction "19_19") (pintype "passive"))
      (node (ref "IN7P3") (pin "SIGNAL") (pinfunction "SIGNAL_SIGNAL") (pintype "bidirectional"))
    )
    (net (code "33") (name "Net-(ELECTRODE-CONNECTOR3-Pad21)") (class "Default")
      (node (ref "ELECTRODE-CONNECTOR3") (pin "21") (pinfunction "21_21") (pintype "passive"))
      (node (ref "IN8P3") (pin "SIGNAL") (pinfunction "SIGNAL_SIGNAL") (pintype "bidirectional"))
    )
    (net (code "34") (name "unconnected-(ELECTRODE-CONNECTOR-Pad1)") (class "Default")
      (node (ref "ELECTRODE-CONNECTOR") (pin "1") (pinfunction "1_1") (pintype "passive"))
    )
    (net (code "35") (name "unconnected-(ELECTRODE-CONNECTOR-Pad2)") (class "Default")
      (node (ref "ELECTRODE-CONNECTOR") (pin "2") (pinfunction "2_2") (pintype "passive"))
    )
    (net (code "36") (name "unconnected-(ELECTRODE-CONNECTOR-Pad3)") (class "Default")
      (node (ref "ELECTRODE-CONNECTOR") (pin "3") (pinfunction "3_3") (pintype "passive"))
    )
    (net (code "37") (name "unconnected-(ELECTRODE-CONNECTOR-Pad23)") (class "Default")
      (node (ref "ELECTRODE-CONNECTOR") (pin "23") (pinfunction "23_23") (pintype "passive"))
    )
    (net (code "38") (name "unconnected-(ELECTRODE-CONNECTOR-Pad24)") (class "Default")
      (node (ref "ELECTRODE-CONNECTOR") (pin "24") (pinfunction "24_24") (pintype "passive"))
    )
    (net (code "39") (name "unconnected-(ELECTRODE-CONNECTOR1-Pad1)") (class "Default")
      (node (ref "ELECTRODE-CONNECTOR1") (pin "1") (pinfunction "1_1") (pintype "passive"))
    )
    (net (code "40") (name "unconnected-(ELECTRODE-CONNECTOR1-Pad2)") (class "Default")
      (node (ref "ELECTRODE-CONNECTOR1") (pin "2") (pinfunction "2_2") (pintype "passive"))
    )
    (net (code "41") (name "unconnected-(ELECTRODE-CONNECTOR1-Pad3)") (class "Default")
      (node (ref "ELECTRODE-CONNECTOR1") (pin "3") (pinfunction "3_3") (pintype "passive"))
    )
    (net (code "42") (name "unconnected-(ELECTRODE-CONNECTOR1-Pad23)") (class "Default")
      (node (ref "ELECTRODE-CONNECTOR1") (pin "23") (pinfunction "23_23") (pintype "passive"))
    )
    (net (code "43") (name "unconnected-(ELECTRODE-CONNECTOR1-Pad24)") (class "Default")
      (node (ref "ELECTRODE-CONNECTOR1") (pin "24") (pinfunction "24_24") (pintype "passive"))
    )
    (net (code "44") (name "unconnected-(ELECTRODE-CONNECTOR2-Pad1)") (class "Default")
      (node (ref "ELECTRODE-CONNECTOR2") (pin "1") (pinfunction "1_1") (pintype "passive"))
    )
    (net (code "45") (name "unconnected-(ELECTRODE-CONNECTOR2-Pad2)") (class "Default")
      (node (ref "ELECTRODE-CONNECTOR2") (pin "2") (pinfunction "2_2") (pintype "passive"))
    )
    (net (code "46") (name "unconnected-(ELECTRODE-CONNECTOR2-Pad3)") (class "Default")
      (node (ref "ELECTRODE-CONNECTOR2") (pin "3") (pinfunction "3_3") (pintype "passive"))
    )
    (net (code "47") (name "unconnected-(ELECTRODE-CONNECTOR2-Pad23)") (class "Default")
      (node (ref "ELECTRODE-CONNECTOR2") (pin "23") (pinfunction "23_23") (pintype "passive"))
    )
    (net (code "48") (name "unconnected-(ELECTRODE-CONNECTOR2-Pad24)") (class "Default")
      (node (ref "ELECTRODE-CONNECTOR2") (pin "24") (pinfunction "24_24") (pintype "passive"))
    )
    (net (code "49") (name "unconnected-(ELECTRODE-CONNECTOR3-Pad1)") (class "Default")
      (node (ref "ELECTRODE-CONNECTOR3") (pin "1") (pinfunction "1_1") (pintype "passive"))
    )
    (net (code "50") (name "unconnected-(ELECTRODE-CONNECTOR3-Pad2)") (class "Default")
      (node (ref "ELECTRODE-CONNECTOR3") (pin "2") (pinfunction "2_2") (pintype "passive"))
    )
    (net (code "51") (name "unconnected-(ELECTRODE-CONNECTOR3-Pad3)") (class "Default")
      (node (ref "ELECTRODE-CONNECTOR3") (pin "3") (pinfunction "3_3") (pintype "passive"))
    )
    (net (code "52") (name "unconnected-(ELECTRODE-CONNECTOR3-Pad23)") (class "Default")
      (node (ref "ELECTRODE-CONNECTOR3") (pin "23") (pinfunction "23_23") (pintype "passive"))
    )
    (net (code "53") (name "unconnected-(ELECTRODE-CONNECTOR3-Pad24)") (class "Default")
      (node (ref "ELECTRODE-CONNECTOR3") (pin "24") (pinfunction "24_24") (pintype "passive"))
    )
  )
)
